# Alimentacion.net
KiCad netlist of a schematic drawn in Altium Designer
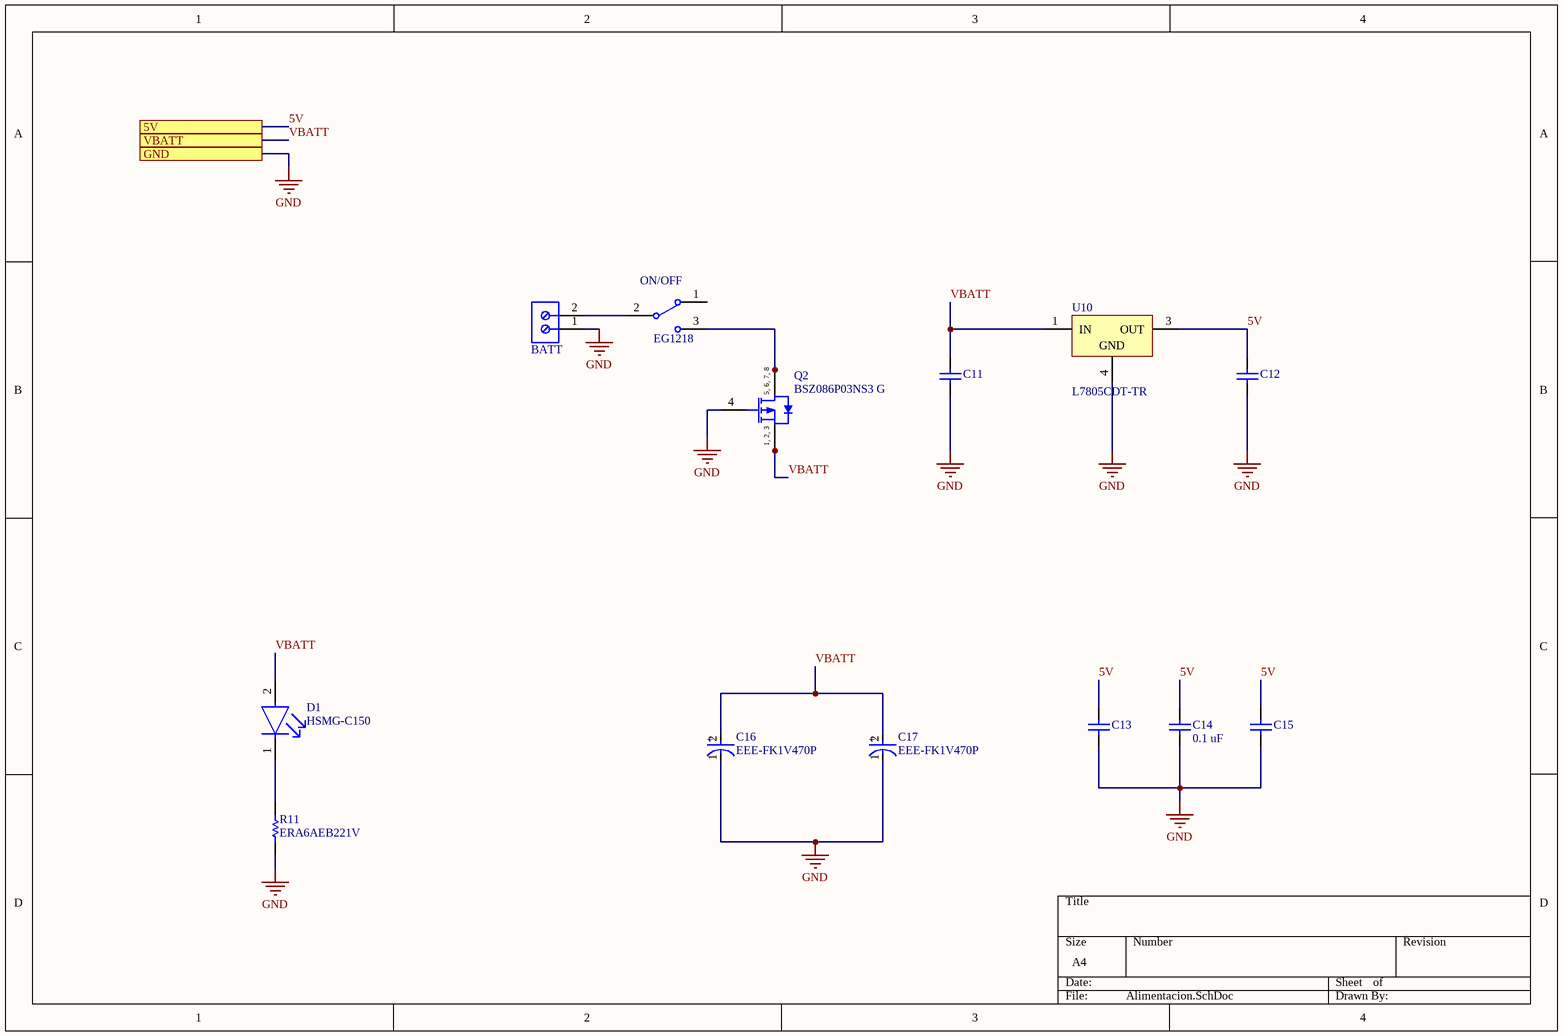
[diagram p0: Alimentacion.SchDoc]

(export (version "E")
  (design (tool "Eeschema 10.0.6"))
  (components
    (comp (ref "BATT")
      (value "691214110002")
      (footprint "691214110002")
      (description "Serie 2141 - 3.50 mm Horizontal Entry Modular with Rising Cage Clamp WR-TBL, 2 pin")
      (fields (field (name "MANUFACTURER") "Wurth Elektronik") (field (name "PUBLISHER") "WurthElektronik"))
      (libsource (lib "Altium Content Vault") (part "WE-CN-1P-F-TB2"))
    )
    (comp (ref "C11")
      (value "C0805C106K4PACTU")
      (footprint "CAPC2013X140X50ML20T25")
      (description "10µF ±10% 16V Ceramic Capacitor X5R 0805 (2012 Metric)")
      (fields (field (name "PART NUMBER") "CL21A106KOQNNNG"))
      (libsource (lib "Altium Content Vault") (part "CAP"))
    )
    (comp (ref "C12")
      (value "C0805C106K4PACTU")
      (footprint "CAPC2013X140X50ML20T25")
      (description "10µF ±10% 16V Ceramic Capacitor X5R 0805 (2012 Metric)")
      (fields (field (name "PART NUMBER") "CL21A106KOQNNNG"))
      (libsource (lib "Altium Content Vault") (part "CAP"))
    )
    (comp (ref "C13")
      (value "C0805C106K4PACTU")
      (footprint "CAPC2013X140X50ML20T25")
      (description "10µF ±10% 16V Ceramic Capacitor X5R 0805 (2012 Metric)")
      (fields (field (name "PART NUMBER") "CL21A106KOQNNNG"))
      (libsource (lib "Altium Content Vault") (part "CAP"))
    )
    (comp (ref "C14")
      (value "0.1 uF")
      (footprint "CAPC2013X94X50ML20T25")
      (description "Chip Capacitor, Ceramic, 0.1 uF, 10%, 50 V, 0805, RoHS, Tape and Reel")
      (fields (field (name "MANUFACTURER") "AVX"))
      (libsource (lib "Altium Content Vault") (part "CAP-NP-2"))
    )
    (comp (ref "C15")
      (value "C0805C106K4PACTU")
      (footprint "CAPC2013X140X50ML20T25")
      (description "10µF ±10% 16V Ceramic Capacitor X5R 0805 (2012 Metric)")
      (fields (field (name "PART NUMBER") "CL21A106KOQNNNG"))
      (libsource (lib "Altium Content Vault") (part "CAP"))
    )
    (comp (ref "C16")
      (value "EEE-FK1V470P")
      (footprint "FP-FK-D-MFG")
      (description "CAP ALUM 47UF 20% 35V SMD")
      (fields
        (field (name "MANUFACTURER") "Panasonic")
        (field (name "OCTOPART") "https://octopart.com/eeefk1v470p-panasonic-4642848")
      )
      (libsource (lib "Altium Content Vault") (part "a00bbbee19879c290e62620ae7e47b1"))
    )
    (comp (ref "C17")
      (value "EEE-FK1V470P")
      (footprint "FP-FK-D-MFG")
      (description "CAP ALUM 47UF 20% 35V SMD")
      (fields
        (field (name "MANUFACTURER") "Panasonic")
        (field (name "OCTOPART") "https://octopart.com/eeefk1v470p-panasonic-4642848")
      )
      (libsource (lib "Altium Content Vault") (part "a00bbbee19879c290e62620ae7e47b1"))
    )
    (comp (ref "D1")
      (value "HSMG-C150")
      (footprint "FP-HSMG-C150-MFG")
      (description "LED GREEN DIFFUSED 1206 SMD")
      (fields
        (field (name "MANUFACTURER") "Broadcom")
        (field (name "OCTOPART") "https://octopart.com/hsmg-c150-broadcom-71131304")
      )
      (libsource (lib "Altium Content Vault") (part "8706943c75ba83719d021d2fdc84c58"))
    )
    (comp (ref "ON/OFF")
      (value "EG1218")
      (footprint "ESWI-EG1218_V")
      (description "Slide Switch, 500 V, -20 to 70 degC, 3-Pin THD, RoHS")
      (libsource (lib "Altium Content Vault") (part "SW-SPDT-3_B"))
    )
    (comp (ref "Q2")
      (value "BSZ086P03NS3 G")
      (footprint "INF-PG-TSDSON-8-1_V")
      (fields (field (name "MANUFACTURER") "Infineon"))
      (libsource (lib "Altium Content Vault") (part "INF-PEMOS-SSSGDDDD-8"))
    )
    (comp (ref "R11")
      (value "ERA6AEB221V")
      (footprint "RESC2013X60X40ML20T25")
      (fields (field (name "MANUFACTURER") "Panasonic"))
      (libsource (lib "Altium Content Vault") (part "RES"))
    )
    (comp (ref "U10")
      (value "L7805CDT-TR")
      (footprint "TO-252_M")
      (description "Positive Voltage Regulator, 3-Pin DPAK, Tape and Reel")
      (libsource (lib "Altium Content Vault") (part "PM-REG-L4940-SOT3"))
    )
  )
  (nets
    (net (code "1") (name "/5V") (class "Default")
      (node (ref "C12") (pin "2") (pinfunction "2_2") (pintype "passive"))
      (node (ref "C13") (pin "2") (pinfunction "2_2") (pintype "passive"))
      (node (ref "C14") (pin "2") (pinfunction "2_2") (pintype "passive"))
      (node (ref "C15") (pin "2") (pinfunction "2_2") (pintype "passive"))
      (node (ref "U10") (pin "3") (pinfunction "OUT_3") (pintype "power_in"))
    )
    (net (code "2") (name "/VBATT") (class "Default")
      (node (ref "C11") (pin "2") (pinfunction "2_2") (pintype "passive"))
      (node (ref "C16") (pin "2") (pinfunction "A_2") (pintype "passive"))
      (node (ref "C17") (pin "2") (pinfunction "A_2") (pintype "passive"))
      (node (ref "D1") (pin "2") (pinfunction "A_2") (pintype "passive"))
      (node (ref "Q2") (pin "1") (pinfunction "SOURCE_1") (pintype "passive"))
      (node (ref "Q2") (pin "2") (pinfunction "SOURCE_2") (pintype "passive"))
      (node (ref "Q2") (pin "3") (pinfunction "SOURCE_3") (pintype "passive"))
      (node (ref "U10") (pin "1") (pinfunction "IN_1") (pintype "power_in"))
    )
    (net (code "3") (name "GND") (class "Default")
      (node (ref "BATT") (pin "1") (pinfunction "1_1") (pintype "passive"))
      (node (ref "C11") (pin "1") (pinfunction "1_1") (pintype "passive"))
      (node (ref "C12") (pin "1") (pinfunction "1_1") (pintype "passive"))
      (node (ref "C13") (pin "1") (pinfunction "1_1") (pintype "passive"))
      (node (ref "C14") (pin "1") (pinfunction "1_1") (pintype "passive"))
      (node (ref "C15") (pin "1") (pinfunction "1_1") (pintype "passive"))
      (node (ref "C16") (pin "1") (pinfunction "C_1") (pintype "passive"))
      (node (ref "C17") (pin "1") (pinfunction "C_1") (pintype "passive"))
      (node (ref "Q2") (pin "4") (pinfunction "GATE_4") (pintype "passive"))
      (node (ref "R11") (pin "1") (pinfunction "1_1") (pintype "passive"))
      (node (ref "U10") (pin "4") (pinfunction "GND_4") (pintype "power_in"))
    )
    (net (code "4") (name "Net-(D1-C)") (class "Default")
      (node (ref "D1") (pin "1") (pinfunction "C_1") (pintype "passive"))
      (node (ref "R11") (pin "2") (pinfunction "2_2") (pintype "passive"))
    )
    (net (code "5") (name "Net-(ON/OFF-COM)") (class "Default")
      (node (ref "BATT") (pin "2") (pinfunction "2_2") (pintype "passive"))
      (node (ref "ON/OFF") (pin "2") (pinfunction "COM_2") (pintype "passive"))
    )
    (net (code "6") (name "Net-(ON/OFF-Pad3)") (class "Default")
      (node (ref "ON/OFF") (pin "3") (pinfunction "3_3") (pintype "passive"))
      (node (ref "Q2") (pin "5") (pinfunction "DRAIN_5") (pintype "passive"))
      (node (ref "Q2") (pin "6") (pinfunction "DRAIN_6") (pintype "passive"))
      (node (ref "Q2") (pin "7") (pinfunction "DRAIN_7") (pintype "passive"))
      (node (ref "Q2") (pin "8") (pinfunction "DRAIN_8") (pintype "passive"))
    )
    (net (code "7") (name "unconnected-(ON/OFF-Pad1)") (class "Default")
      (node (ref "ON/OFF") (pin "1") (pinfunction "1_1") (pintype "passive"))
    )
  )
)
